# MCU4Insole.net
KiCad netlist of a schematic drawn in EasyEDA
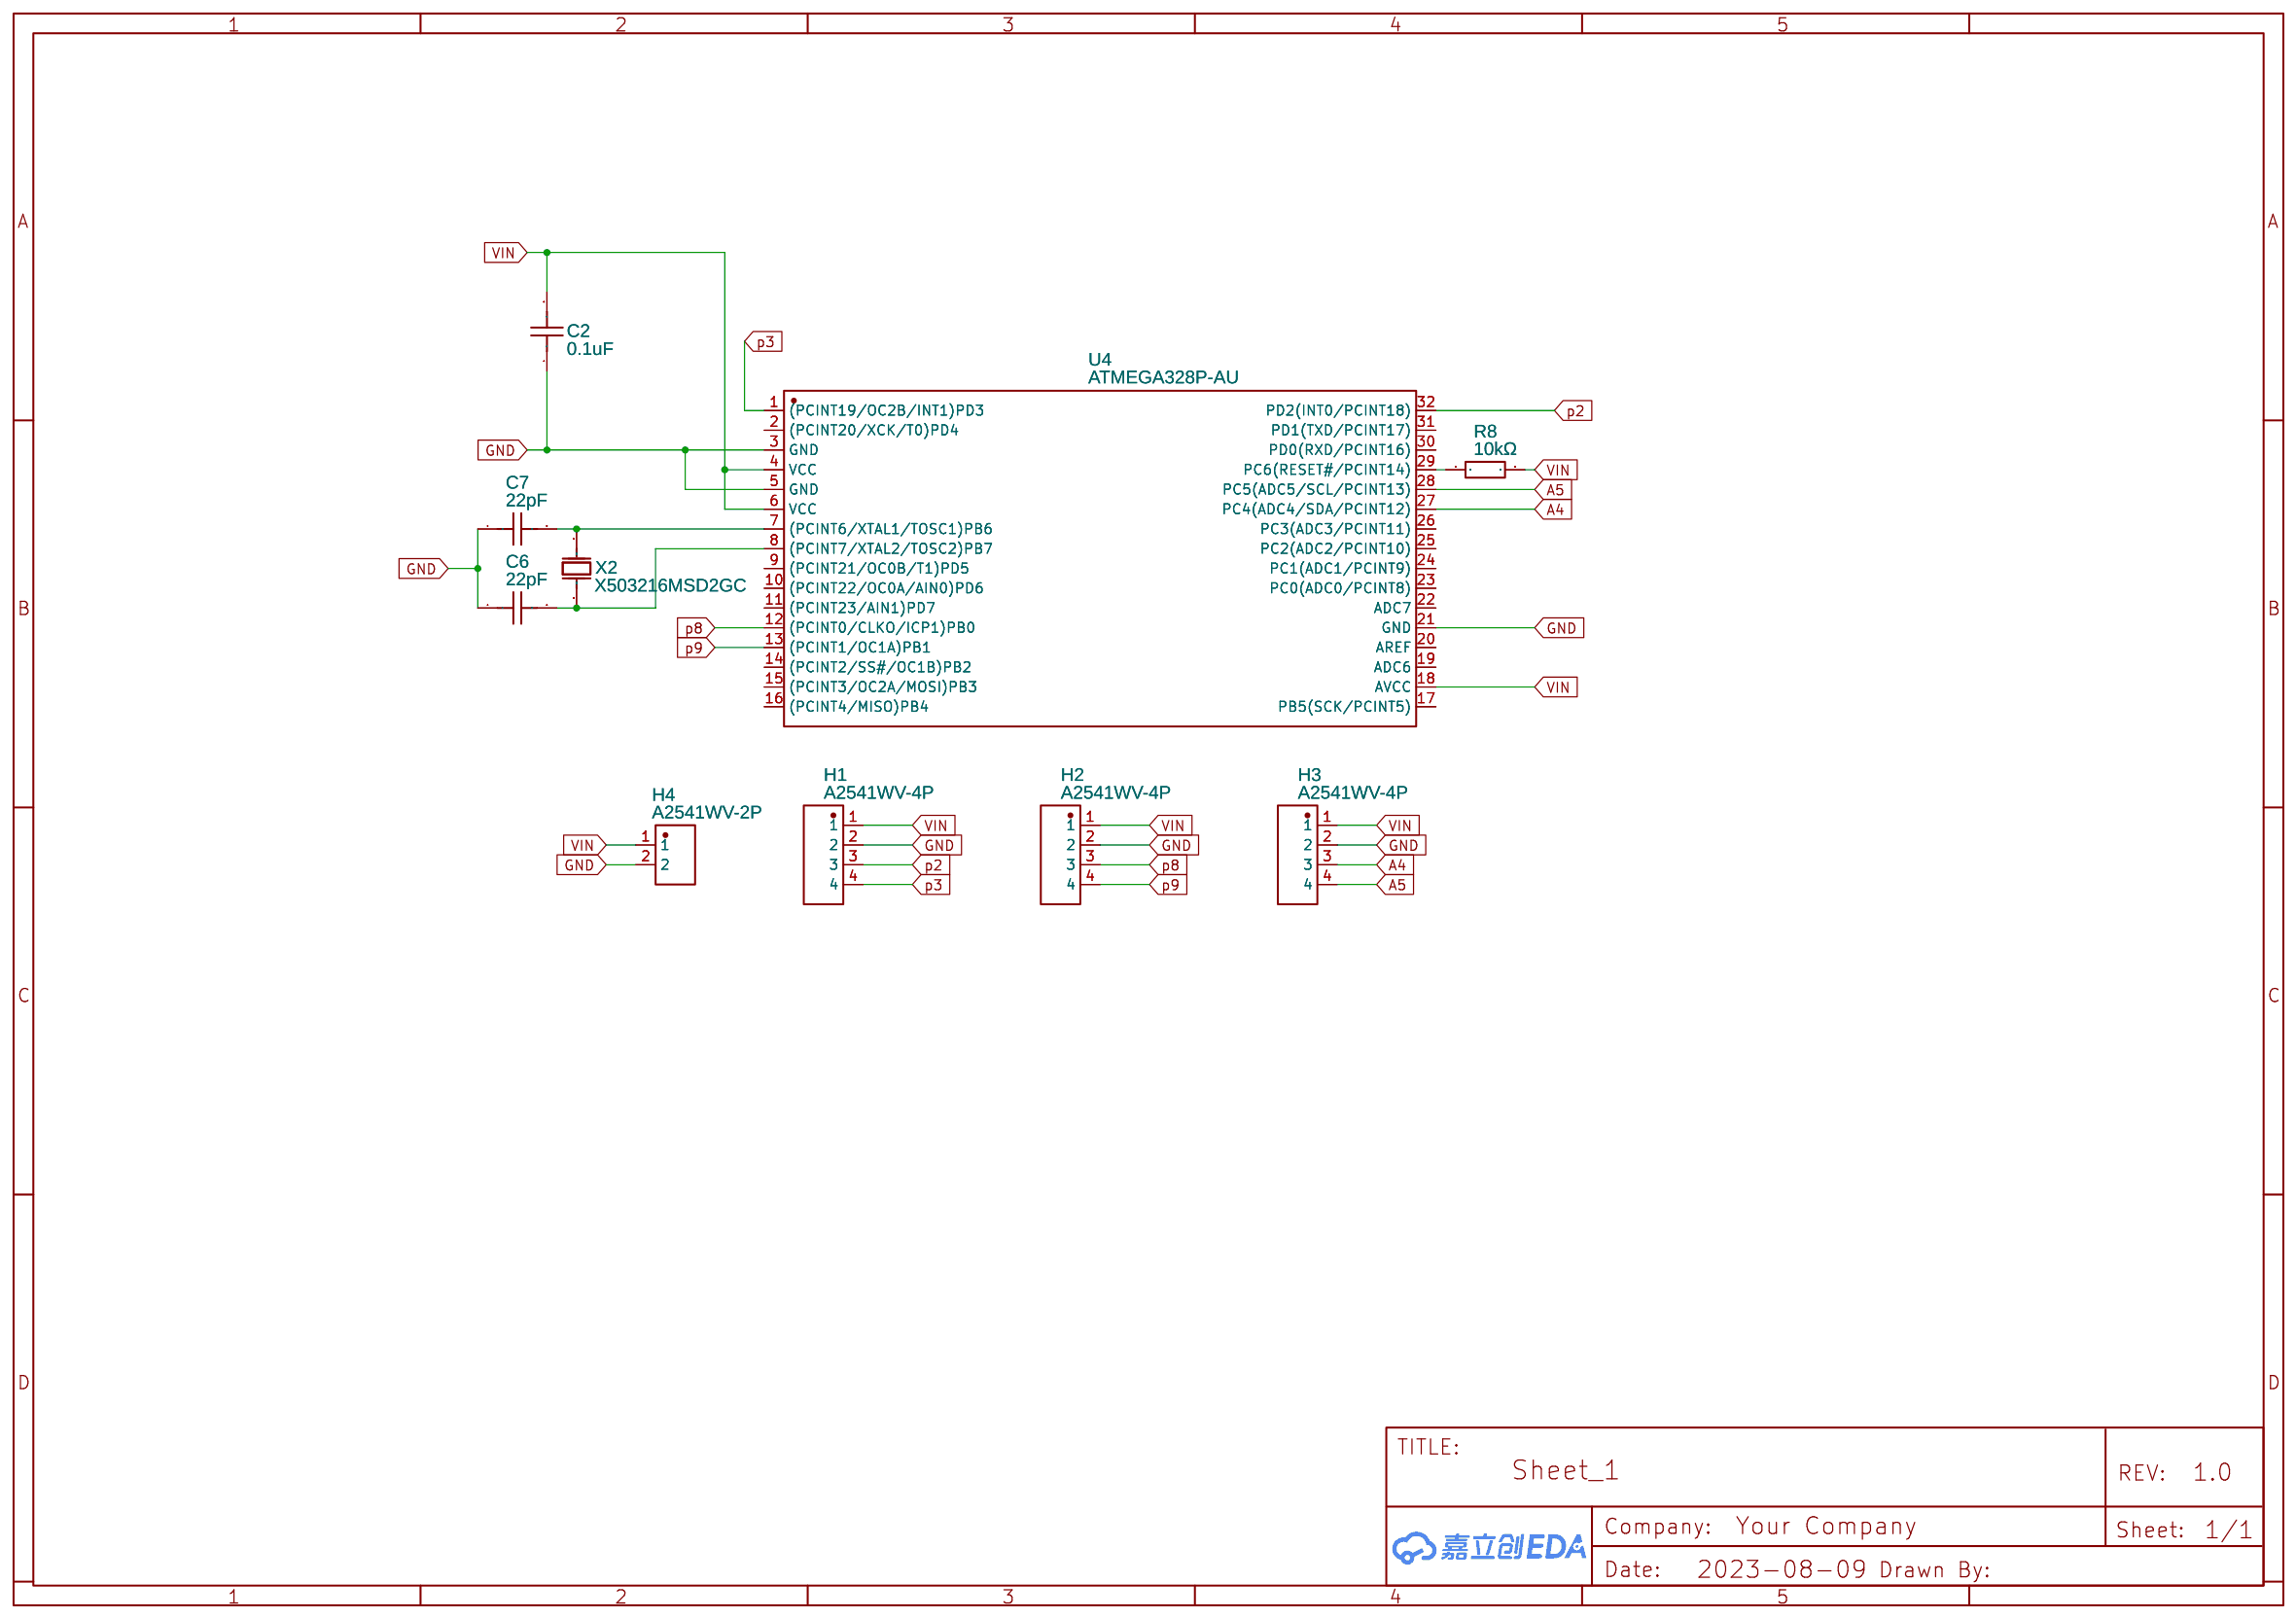
[diagram p0: schematic sheet]

(export (version "E")
  (design (tool "Eeschema 10.0.6"))
  (components
    (comp (ref "C2")
      (value "0.1uF")
      (fields
        (field (name "BOM_Manufacturer Part") "0603BB104K500NGT")
        (field (name "BOM_Supplier Part") "C2168571")
      )
      (libsource (lib "") (part "0603BB104K500NGT"))
    )
    (comp (ref "C6")
      (value "22pF")
      (fields
        (field (name "BOM_Manufacturer Part") "C0603C220J5GACAUTO")
        (field (name "BOM_Supplier Part") "C599692")
      )
      (libsource (lib "") (part "C0603C220J5GACAUTO"))
    )
    (comp (ref "C7")
      (value "22pF")
      (fields
        (field (name "BOM_Manufacturer Part") "C0603C220J5GACAUTO")
        (field (name "BOM_Supplier Part") "C599692")
      )
      (libsource (lib "") (part "C0603C220J5GACAUTO"))
    )
    (comp (ref "H1")
      (value "A2541WV-4P")
      (fields (field (name "Manufacturer") "CJT(长江连接器)"))
      (libsource (lib "") (part "A2541WV-4P"))
    )
    (comp (ref "H2")
      (value "A2541WV-4P")
      (fields (field (name "Manufacturer") "CJT(长江连接器)"))
      (libsource (lib "") (part "A2541WV-4P"))
    )
    (comp (ref "H3")
      (value "A2541WV-4P")
      (fields (field (name "Manufacturer") "CJT(长江连接器)"))
      (libsource (lib "") (part "A2541WV-4P"))
    )
    (comp (ref "H4")
      (value "A2541WV-2P")
      (fields (field (name "Manufacturer") "CJT(长江连接器)"))
      (libsource (lib "") (part "A2541WV-2P"))
    )
    (comp (ref "R8")
      (value "10kΩ")
      (fields
        (field (name "BOM_Manufacturer Part") "ETCR0603F10K0K9")
        (field (name "BOM_Supplier Part") "C365375")
      )
      (libsource (lib "") (part "ETCR0603F10K0K9"))
    )
    (comp (ref "U4")
      (value "ATMEGA328P-AU")
      (fields (field (name "BOM_Supplier Part") "C14877"))
      (libsource (lib "") (part "ATMEGA328P-AU"))
    )
    (comp (ref "X2")
      (value "X503216MSD2GC")
      (fields (field (name "BOM_Supplier Part") "C49231"))
      (libsource (lib "") (part "X503216MSD2GC"))
    )
  )
  (nets
    (net (code "1") (name "A4") (class "Default")
      (node (ref "H3") (pin "3") (pinfunction "3_3") (pintype "unspecified"))
      (node (ref "U4") (pin "27") (pinfunction "PC4(ADC4/SDA/PCINT12)_27") (pintype "unspecified"))
    )
    (net (code "2") (name "A5") (class "Default")
      (node (ref "H3") (pin "4") (pinfunction "4_4") (pintype "unspecified"))
      (node (ref "U4") (pin "28") (pinfunction "PC5(ADC5/SCL/PCINT13)_28") (pintype "unspecified"))
    )
    (net (code "3") (name "GND") (class "Default")
      (node (ref "C2") (pin "1") (pinfunction "1_1") (pintype "unspecified"))
      (node (ref "C6") (pin "1") (pinfunction "1_1") (pintype "unspecified"))
      (node (ref "C7") (pin "1") (pinfunction "1_1") (pintype "unspecified"))
      (node (ref "H1") (pin "2") (pinfunction "2_2") (pintype "unspecified"))
      (node (ref "H2") (pin "2") (pinfunction "2_2") (pintype "unspecified"))
      (node (ref "H3") (pin "2") (pinfunction "2_2") (pintype "unspecified"))
      (node (ref "H4") (pin "2") (pinfunction "2_2") (pintype "unspecified"))
      (node (ref "U4") (pin "21") (pinfunction "GND_21") (pintype "unspecified"))
      (node (ref "U4") (pin "3") (pinfunction "GND_3") (pintype "unspecified"))
      (node (ref "U4") (pin "5") (pinfunction "GND_5") (pintype "unspecified"))
    )
    (net (code "4") (name "Net-(U4-(PCINT6{slash}XTAL1{slash}TOSC1)PB6)") (class "Default")
      (node (ref "C7") (pin "2") (pinfunction "2_2") (pintype "unspecified"))
      (node (ref "U4") (pin "7") (pinfunction "(PCINT6/XTAL1/TOSC1)PB6_7") (pintype "unspecified"))
      (node (ref "X2") (pin "1") (pinfunction "OSC1_1") (pintype "input"))
    )
    (net (code "5") (name "Net-(U4-(PCINT7{slash}XTAL2{slash}TOSC2)PB7)") (class "Default")
      (node (ref "C6") (pin "2") (pinfunction "2_2") (pintype "unspecified"))
      (node (ref "U4") (pin "8") (pinfunction "(PCINT7/XTAL2/TOSC2)PB7_8") (pintype "unspecified"))
      (node (ref "X2") (pin "2") (pinfunction "OSC2_2") (pintype "input"))
    )
    (net (code "6") (name "Net-(U4-PC6(RESET#{slash}PCINT14))") (class "Default")
      (node (ref "R8") (pin "1") (pinfunction "1_1") (pintype "unspecified"))
      (node (ref "U4") (pin "29") (pinfunction "PC6(RESET#/PCINT14)_29") (pintype "unspecified"))
    )
    (net (code "7") (name "VIN") (class "Default")
      (node (ref "C2") (pin "2") (pinfunction "2_2") (pintype "unspecified"))
      (node (ref "H1") (pin "1") (pinfunction "1_1") (pintype "unspecified"))
      (node (ref "H2") (pin "1") (pinfunction "1_1") (pintype "unspecified"))
      (node (ref "H3") (pin "1") (pinfunction "1_1") (pintype "unspecified"))
      (node (ref "H4") (pin "1") (pinfunction "1_1") (pintype "unspecified"))
      (node (ref "R8") (pin "2") (pinfunction "2_2") (pintype "unspecified"))
      (node (ref "U4") (pin "18") (pinfunction "AVCC_18") (pintype "unspecified"))
      (node (ref "U4") (pin "4") (pinfunction "VCC_4") (pintype "unspecified"))
      (node (ref "U4") (pin "6") (pinfunction "VCC_6") (pintype "unspecified"))
    )
    (net (code "8") (name "p2") (class "Default")
      (node (ref "H1") (pin "3") (pinfunction "3_3") (pintype "unspecified"))
      (node (ref "U4") (pin "32") (pinfunction "PD2(INT0/PCINT18)_32") (pintype "unspecified"))
    )
    (net (code "9") (name "p3") (class "Default")
      (node (ref "H1") (pin "4") (pinfunction "4_4") (pintype "unspecified"))
      (node (ref "U4") (pin "1") (pinfunction "(PCINT19/OC2B/INT1)PD3_1") (pintype "unspecified"))
    )
    (net (code "10") (name "p8") (class "Default")
      (node (ref "H2") (pin "3") (pinfunction "3_3") (pintype "unspecified"))
      (node (ref "U4") (pin "12") (pinfunction "(PCINT0/CLKO/ICP1)PB0_12") (pintype "unspecified"))
    )
    (net (code "11") (name "p9") (class "Default")
      (node (ref "H2") (pin "4") (pinfunction "4_4") (pintype "unspecified"))
      (node (ref "U4") (pin "13") (pinfunction "(PCINT1/OC1A)PB1_13") (pintype "unspecified"))
    )
    (net (code "12") (name "unconnected-(U4-(PCINT2{slash}SS#{slash}OC1B)PB2-Pad14)") (class "Default")
      (node (ref "U4") (pin "14") (pinfunction "(PCINT2/SS#/OC1B)PB2_14") (pintype "unspecified"))
    )
    (net (code "13") (name "unconnected-(U4-(PCINT3{slash}OC2A{slash}MOSI)PB3-Pad15)") (class "Default")
      (node (ref "U4") (pin "15") (pinfunction "(PCINT3/OC2A/MOSI)PB3_15") (pintype "unspecified"))
    )
    (net (code "14") (name "unconnected-(U4-(PCINT4{slash}MISO)PB4-Pad16)") (class "Default")
      (node (ref "U4") (pin "16") (pinfunction "(PCINT4/MISO)PB4_16") (pintype "unspecified"))
    )
    (net (code "15") (name "unconnected-(U4-(PCINT20{slash}XCK{slash}T0)PD4-Pad2)") (class "Default")
      (node (ref "U4") (pin "2") (pinfunction "(PCINT20/XCK/T0)PD4_2") (pintype "unspecified"))
    )
    (net (code "16") (name "unconnected-(U4-(PCINT21{slash}OC0B{slash}T1)PD5-Pad9)") (class "Default")
      (node (ref "U4") (pin "9") (pinfunction "(PCINT21/OC0B/T1)PD5_9") (pintype "unspecified"))
    )
    (net (code "17") (name "unconnected-(U4-(PCINT22{slash}OC0A{slash}AIN0)PD6-Pad10)") (class "Default")
      (node (ref "U4") (pin "10") (pinfunction "(PCINT22/OC0A/AIN0)PD6_10") (pintype "unspecified"))
    )
    (net (code "18") (name "unconnected-(U4-(PCINT23{slash}AIN1)PD7-Pad11)") (class "Default")
      (node (ref "U4") (pin "11") (pinfunction "(PCINT23/AIN1)PD7_11") (pintype "unspecified"))
    )
    (net (code "19") (name "unconnected-(U4-ADC6-Pad19)") (class "Default")
      (node (ref "U4") (pin "19") (pinfunction "ADC6_19") (pintype "unspecified"))
    )
    (net (code "20") (name "unconnected-(U4-ADC7-Pad22)") (class "Default")
      (node (ref "U4") (pin "22") (pinfunction "ADC7_22") (pintype "unspecified"))
    )
    (net (code "21") (name "unconnected-(U4-AREF-Pad20)") (class "Default")
      (node (ref "U4") (pin "20") (pinfunction "AREF_20") (pintype "unspecified"))
    )
    (net (code "22") (name "unconnected-(U4-PB5(SCK{slash}PCINT5)-Pad17)") (class "Default")
      (node (ref "U4") (pin "17") (pinfunction "PB5(SCK/PCINT5)_17") (pintype "unspecified"))
    )
    (net (code "23") (name "unconnected-(U4-PC0(ADC0{slash}PCINT8)-Pad23)") (class "Default")
      (node (ref "U4") (pin "23") (pinfunction "PC0(ADC0/PCINT8)_23") (pintype "unspecified"))
    )
    (net (code "24") (name "unconnected-(U4-PC1(ADC1{slash}PCINT9)-Pad24)") (class "Default")
      (node (ref "U4") (pin "24") (pinfunction "PC1(ADC1/PCINT9)_24") (pintype "unspecified"))
    )
    (net (code "25") (name "unconnected-(U4-PC2(ADC2{slash}PCINT10)-Pad25)") (class "Default")
      (node (ref "U4") (pin "25") (pinfunction "PC2(ADC2/PCINT10)_25") (pintype "unspecified"))
    )
    (net (code "26") (name "unconnected-(U4-PC3(ADC3{slash}PCINT11)-Pad26)") (class "Default")
      (node (ref "U4") (pin "26") (pinfunction "PC3(ADC3/PCINT11)_26") (pintype "unspecified"))
    )
    (net (code "27") (name "unconnected-(U4-PD0(RXD{slash}PCINT16)-Pad30)") (class "Default")
      (node (ref "U4") (pin "30") (pinfunction "PD0(RXD/PCINT16)_30") (pintype "unspecified"))
    )
    (net (code "28") (name "unconnected-(U4-PD1(TXD{slash}PCINT17)-Pad31)") (class "Default")
      (node (ref "U4") (pin "31") (pinfunction "PD1(TXD/PCINT17)_31") (pintype "unspecified"))
    )
  )
)
